# M101X.net
KiCad netlist of a schematic drawn in EAGLE
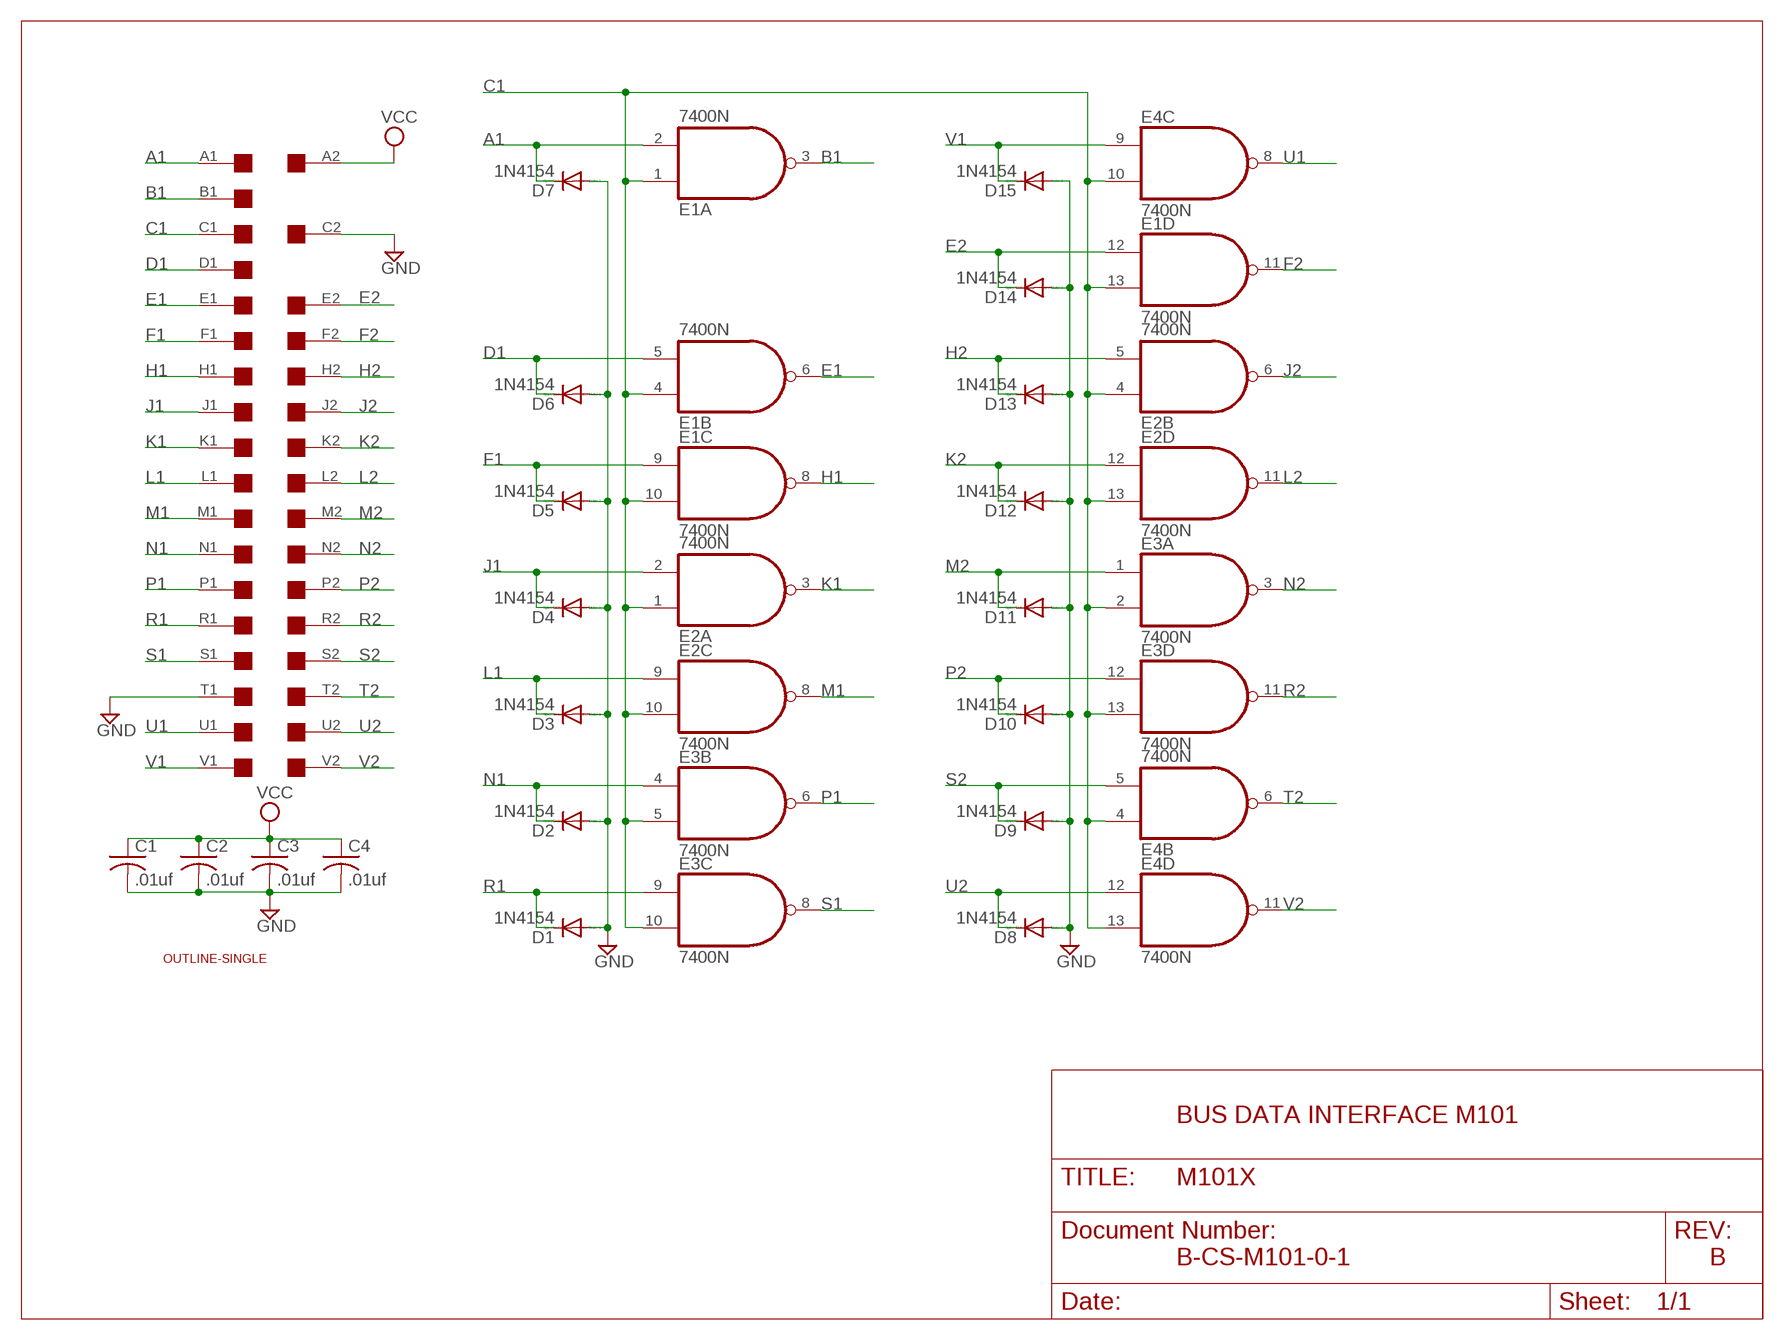
[diagram p0: schematic, sheet 1]

(export (version "E")
  (design (tool "Eeschema 10.0.6"))
  (components
    (comp (ref "C1")
      (value ".01uf")
      (footprint "eagle-import:C050-025X075")
      (libsource (lib "eagle-import") (part "C-US050-025X075"))
    )
    (comp (ref "C2")
      (value ".01uf")
      (footprint "eagle-import:C050-025X075")
      (libsource (lib "eagle-import") (part "C-US050-025X075"))
    )
    (comp (ref "C3")
      (value ".01uf")
      (footprint "eagle-import:C050-025X075")
      (libsource (lib "eagle-import") (part "C-US050-025X075"))
    )
    (comp (ref "C4")
      (value ".01uf")
      (footprint "eagle-import:C050-025X075")
      (libsource (lib "eagle-import") (part "C-US050-025X075"))
    )
    (comp (ref "D1")
      (value "1N4154")
      (footprint "eagle-import:DO35-10")
      (libsource (lib "eagle-import") (part "1N4148DO35-10"))
    )
    (comp (ref "D2")
      (value "1N4154")
      (footprint "eagle-import:DO35-10")
      (libsource (lib "eagle-import") (part "1N4148DO35-10"))
    )
    (comp (ref "D3")
      (value "1N4154")
      (footprint "eagle-import:DO35-10")
      (libsource (lib "eagle-import") (part "1N4148DO35-10"))
    )
    (comp (ref "D4")
      (value "1N4154")
      (footprint "eagle-import:DO35-10")
      (libsource (lib "eagle-import") (part "1N4148DO35-10"))
    )
    (comp (ref "D5")
      (value "1N4154")
      (footprint "eagle-import:DO35-10")
      (libsource (lib "eagle-import") (part "1N4148DO35-10"))
    )
    (comp (ref "D6")
      (value "1N4154")
      (footprint "eagle-import:DO35-10")
      (libsource (lib "eagle-import") (part "1N4148DO35-10"))
    )
    (comp (ref "D7")
      (value "1N4154")
      (footprint "eagle-import:DO35-10")
      (libsource (lib "eagle-import") (part "1N4148DO35-10"))
    )
    (comp (ref "D8")
      (value "1N4154")
      (footprint "eagle-import:DO35-10")
      (libsource (lib "eagle-import") (part "1N4148DO35-10"))
    )
    (comp (ref "D9")
      (value "1N4154")
      (footprint "eagle-import:DO35-10")
      (libsource (lib "eagle-import") (part "1N4148DO35-10"))
    )
    (comp (ref "D10")
      (value "1N4154")
      (footprint "eagle-import:DO35-10")
      (libsource (lib "eagle-import") (part "1N4148DO35-10"))
    )
    (comp (ref "D11")
      (value "1N4154")
      (footprint "eagle-import:DO35-10")
      (libsource (lib "eagle-import") (part "1N4148DO35-10"))
    )
    (comp (ref "D12")
      (value "1N4154")
      (footprint "eagle-import:DO35-10")
      (libsource (lib "eagle-import") (part "1N4148DO35-10"))
    )
    (comp (ref "D13")
      (value "1N4154")
      (footprint "eagle-import:DO35-10")
      (libsource (lib "eagle-import") (part "1N4148DO35-10"))
    )
    (comp (ref "D14")
      (value "1N4154")
      (footprint "eagle-import:DO35-10")
      (libsource (lib "eagle-import") (part "1N4148DO35-10"))
    )
    (comp (ref "D15")
      (value "1N4154")
      (footprint "eagle-import:DO35-10")
      (libsource (lib "eagle-import") (part "1N4148DO35-10"))
    )
    (comp (ref "E1")
      (value "7400N")
      (footprint "eagle-import:DIL14")
      (libsource (lib "eagle-import") (part "7400N"))
    )
    (comp (ref "E2")
      (value "7400N")
      (footprint "eagle-import:DIL14")
      (libsource (lib "eagle-import") (part "7400N"))
    )
    (comp (ref "E3")
      (value "7400N")
      (footprint "eagle-import:DIL14")
      (libsource (lib "eagle-import") (part "7400N"))
    )
    (comp (ref "E4")
      (value "7400N")
      (footprint "eagle-import:DIL14")
      (libsource (lib "eagle-import") (part "7400N"))
    )
    (comp (ref "U$1")
      (value "SINGLE")
      (footprint "eagle-import:EDGE-CON2")
      (libsource (lib "eagle-import") (part "SINGLE"))
    )
    (comp (ref "U$4")
      (value "OUTLINE-SINGLE")
      (footprint "eagle-import:SINGLE")
      (libsource (lib "eagle-import") (part "OUTLINE-SINGLE"))
    )
  )
  (nets
    (net (code "1") (name "/A1") (class "Default")
      (node (ref "D7") (pin "C") (pinfunction "C_C") (pintype "passive"))
      (node (ref "E1") (pin "2") (pinfunction "I1_2") (pintype "input"))
      (node (ref "U$1") (pin "A1") (pinfunction "1_A1") (pintype "bidirectional"))
    )
    (net (code "2") (name "/B1") (class "Default")
      (node (ref "E1") (pin "3") (pinfunction "O_3") (pintype "output"))
      (node (ref "U$1") (pin "B1") (pinfunction "1_B1") (pintype "bidirectional"))
    )
    (net (code "3") (name "/C1") (class "Default")
      (node (ref "E1") (pin "1") (pinfunction "I0_1") (pintype "input"))
      (node (ref "E1") (pin "10") (pinfunction "I1_10") (pintype "input"))
      (node (ref "E1") (pin "13") (pinfunction "I1_13") (pintype "input"))
      (node (ref "E1") (pin "4") (pinfunction "I0_4") (pintype "input"))
      (node (ref "E2") (pin "1") (pinfunction "I0_1") (pintype "input"))
      (node (ref "E2") (pin "10") (pinfunction "I1_10") (pintype "input"))
      (node (ref "E2") (pin "13") (pinfunction "I1_13") (pintype "input"))
      (node (ref "E2") (pin "4") (pinfunction "I0_4") (pintype "input"))
      (node (ref "E3") (pin "10") (pinfunction "I1_10") (pintype "input"))
      (node (ref "E3") (pin "13") (pinfunction "I1_13") (pintype "input"))
      (node (ref "E3") (pin "2") (pinfunction "I1_2") (pintype "input"))
      (node (ref "E3") (pin "5") (pinfunction "I1_5") (pintype "input"))
      (node (ref "E4") (pin "10") (pinfunction "I1_10") (pintype "input"))
      (node (ref "E4") (pin "13") (pinfunction "I1_13") (pintype "input"))
      (node (ref "E4") (pin "4") (pinfunction "I0_4") (pintype "input"))
      (node (ref "U$1") (pin "C1") (pinfunction "1_C1") (pintype "bidirectional"))
    )
    (net (code "4") (name "/D1") (class "Default")
      (node (ref "D6") (pin "C") (pinfunction "C_C") (pintype "passive"))
      (node (ref "E1") (pin "5") (pinfunction "I1_5") (pintype "input"))
      (node (ref "U$1") (pin "D1") (pinfunction "1_D1") (pintype "bidirectional"))
    )
    (net (code "5") (name "/E1") (class "Default")
      (node (ref "E1") (pin "6") (pinfunction "O_6") (pintype "output"))
      (node (ref "U$1") (pin "E1") (pinfunction "1_E1") (pintype "bidirectional"))
    )
    (net (code "6") (name "/E2") (class "Default")
      (node (ref "D14") (pin "C") (pinfunction "C_C") (pintype "passive"))
      (node (ref "E1") (pin "12") (pinfunction "I0_12") (pintype "input"))
      (node (ref "U$1") (pin "E2") (pinfunction "1_E2") (pintype "bidirectional"))
    )
    (net (code "7") (name "/F1") (class "Default")
      (node (ref "D5") (pin "C") (pinfunction "C_C") (pintype "passive"))
      (node (ref "E1") (pin "9") (pinfunction "I0_9") (pintype "input"))
      (node (ref "U$1") (pin "F1") (pinfunction "1_F1") (pintype "bidirectional"))
    )
    (net (code "8") (name "/F2") (class "Default")
      (node (ref "E1") (pin "11") (pinfunction "O_11") (pintype "output"))
      (node (ref "U$1") (pin "F2") (pinfunction "1_F2") (pintype "bidirectional"))
    )
    (net (code "9") (name "/H1") (class "Default")
      (node (ref "E1") (pin "8") (pinfunction "O_8") (pintype "output"))
      (node (ref "U$1") (pin "H1") (pinfunction "1_H1") (pintype "bidirectional"))
    )
    (net (code "10") (name "/H2") (class "Default")
      (node (ref "D13") (pin "C") (pinfunction "C_C") (pintype "passive"))
      (node (ref "E2") (pin "5") (pinfunction "I1_5") (pintype "input"))
      (node (ref "U$1") (pin "H2") (pinfunction "1_H2") (pintype "bidirectional"))
    )
    (net (code "11") (name "/J1") (class "Default")
      (node (ref "D4") (pin "C") (pinfunction "C_C") (pintype "passive"))
      (node (ref "E2") (pin "2") (pinfunction "I1_2") (pintype "input"))
      (node (ref "U$1") (pin "J1") (pinfunction "1_J1") (pintype "bidirectional"))
    )
    (net (code "12") (name "/J2") (class "Default")
      (node (ref "E2") (pin "6") (pinfunction "O_6") (pintype "output"))
      (node (ref "U$1") (pin "J2") (pinfunction "1_J2") (pintype "bidirectional"))
    )
    (net (code "13") (name "/K1") (class "Default")
      (node (ref "E2") (pin "3") (pinfunction "O_3") (pintype "output"))
      (node (ref "U$1") (pin "K1") (pinfunction "1_K1") (pintype "bidirectional"))
    )
    (net (code "14") (name "/K2") (class "Default")
      (node (ref "D12") (pin "C") (pinfunction "C_C") (pintype "passive"))
      (node (ref "E2") (pin "12") (pinfunction "I0_12") (pintype "input"))
      (node (ref "U$1") (pin "K2") (pinfunction "1_K2") (pintype "bidirectional"))
    )
    (net (code "15") (name "/L1") (class "Default")
      (node (ref "D3") (pin "C") (pinfunction "C_C") (pintype "passive"))
      (node (ref "E2") (pin "9") (pinfunction "I0_9") (pintype "input"))
      (node (ref "U$1") (pin "L1") (pinfunction "1_L1") (pintype "bidirectional"))
    )
    (net (code "16") (name "/L2") (class "Default")
      (node (ref "E2") (pin "11") (pinfunction "O_11") (pintype "output"))
      (node (ref "U$1") (pin "L2") (pinfunction "1_L2") (pintype "bidirectional"))
    )
    (net (code "17") (name "/M1") (class "Default")
      (node (ref "E2") (pin "8") (pinfunction "O_8") (pintype "output"))
      (node (ref "U$1") (pin "M1") (pinfunction "1_M1") (pintype "bidirectional"))
    )
    (net (code "18") (name "/M2") (class "Default")
      (node (ref "D11") (pin "C") (pinfunction "C_C") (pintype "passive"))
      (node (ref "E3") (pin "1") (pinfunction "I0_1") (pintype "input"))
      (node (ref "U$1") (pin "M2") (pinfunction "1_M2") (pintype "bidirectional"))
    )
    (net (code "19") (name "/N1") (class "Default")
      (node (ref "D2") (pin "C") (pinfunction "C_C") (pintype "passive"))
      (node (ref "E3") (pin "4") (pinfunction "I0_4") (pintype "input"))
      (node (ref "U$1") (pin "N1") (pinfunction "1_N1") (pintype "bidirectional"))
    )
    (net (code "20") (name "/N2") (class "Default")
      (node (ref "E3") (pin "3") (pinfunction "O_3") (pintype "output"))
      (node (ref "U$1") (pin "N2") (pinfunction "1_N2") (pintype "bidirectional"))
    )
    (net (code "21") (name "/P1") (class "Default")
      (node (ref "E3") (pin "6") (pinfunction "O_6") (pintype "output"))
      (node (ref "U$1") (pin "P1") (pinfunction "1_P1") (pintype "bidirectional"))
    )
    (net (code "22") (name "/P2") (class "Default")
      (node (ref "D10") (pin "C") (pinfunction "C_C") (pintype "passive"))
      (node (ref "E3") (pin "12") (pinfunction "I0_12") (pintype "input"))
      (node (ref "U$1") (pin "P2") (pinfunction "1_P2") (pintype "bidirectional"))
    )
    (net (code "23") (name "/R1") (class "Default")
      (node (ref "D1") (pin "C") (pinfunction "C_C") (pintype "passive"))
      (node (ref "E3") (pin "9") (pinfunction "I0_9") (pintype "input"))
      (node (ref "U$1") (pin "R1") (pinfunction "1_R1") (pintype "bidirectional"))
    )
    (net (code "24") (name "/R2") (class "Default")
      (node (ref "E3") (pin "11") (pinfunction "O_11") (pintype "output"))
      (node (ref "U$1") (pin "R2") (pinfunction "1_R2") (pintype "bidirectional"))
    )
    (net (code "25") (name "/S1") (class "Default")
      (node (ref "E3") (pin "8") (pinfunction "O_8") (pintype "output"))
      (node (ref "U$1") (pin "S1") (pinfunction "1_S1") (pintype "bidirectional"))
    )
    (net (code "26") (name "/S2") (class "Default")
      (node (ref "D9") (pin "C") (pinfunction "C_C") (pintype "passive"))
      (node (ref "E4") (pin "5") (pinfunction "I1_5") (pintype "input"))
      (node (ref "U$1") (pin "S2") (pinfunction "1_S2") (pintype "bidirectional"))
    )
    (net (code "27") (name "/T2") (class "Default")
      (node (ref "E4") (pin "6") (pinfunction "O_6") (pintype "output"))
      (node (ref "U$1") (pin "T2") (pinfunction "1_T2") (pintype "bidirectional"))
    )
    (net (code "28") (name "/U1") (class "Default")
      (node (ref "E4") (pin "8") (pinfunction "O_8") (pintype "output"))
      (node (ref "U$1") (pin "U1") (pinfunction "1_U1") (pintype "bidirectional"))
    )
    (net (code "29") (name "/U2") (class "Default")
      (node (ref "D8") (pin "C") (pinfunction "C_C") (pintype "passive"))
      (node (ref "E4") (pin "12") (pinfunction "I0_12") (pintype "input"))
      (node (ref "U$1") (pin "U2") (pinfunction "1_U2") (pintype "bidirectional"))
    )
    (net (code "30") (name "/V1") (class "Default")
      (node (ref "D15") (pin "C") (pinfunction "C_C") (pintype "passive"))
      (node (ref "E4") (pin "9") (pinfunction "I0_9") (pintype "input"))
      (node (ref "U$1") (pin "V1") (pinfunction "1_V1") (pintype "bidirectional"))
    )
    (net (code "31") (name "/V2") (class "Default")
      (node (ref "E4") (pin "11") (pinfunction "O_11") (pintype "output"))
      (node (ref "U$1") (pin "V2") (pinfunction "1_V2") (pintype "bidirectional"))
    )
    (net (code "32") (name "GND") (class "Default")
      (node (ref "C1") (pin "2") (pinfunction "2_2") (pintype "passive"))
      (node (ref "C2") (pin "2") (pinfunction "2_2") (pintype "passive"))
      (node (ref "C3") (pin "2") (pinfunction "2_2") (pintype "passive"))
      (node (ref "C4") (pin "2") (pinfunction "2_2") (pintype "passive"))
      (node (ref "D1") (pin "A") (pinfunction "A_A") (pintype "passive"))
      (node (ref "D10") (pin "A") (pinfunction "A_A") (pintype "passive"))
      (node (ref "D11") (pin "A") (pinfunction "A_A") (pintype "passive"))
      (node (ref "D12") (pin "A") (pinfunction "A_A") (pintype "passive"))
      (node (ref "D13") (pin "A") (pinfunction "A_A") (pintype "passive"))
      (node (ref "D14") (pin "A") (pinfunction "A_A") (pintype "passive"))
      (node (ref "D15") (pin "A") (pinfunction "A_A") (pintype "passive"))
      (node (ref "D2") (pin "A") (pinfunction "A_A") (pintype "passive"))
      (node (ref "D3") (pin "A") (pinfunction "A_A") (pintype "passive"))
      (node (ref "D4") (pin "A") (pinfunction "A_A") (pintype "passive"))
      (node (ref "D5") (pin "A") (pinfunction "A_A") (pintype "passive"))
      (node (ref "D6") (pin "A") (pinfunction "A_A") (pintype "passive"))
      (node (ref "D7") (pin "A") (pinfunction "A_A") (pintype "passive"))
      (node (ref "D8") (pin "A") (pinfunction "A_A") (pintype "passive"))
      (node (ref "D9") (pin "A") (pinfunction "A_A") (pintype "passive"))
      (node (ref "U$1") (pin "C2") (pinfunction "1_C2") (pintype "bidirectional"))
      (node (ref "U$1") (pin "T1") (pinfunction "1_T1") (pintype "bidirectional"))
    )
    (net (code "33") (name "VCC") (class "Default")
      (node (ref "C1") (pin "1") (pinfunction "1_1") (pintype "passive"))
      (node (ref "C2") (pin "1") (pinfunction "1_1") (pintype "passive"))
      (node (ref "C3") (pin "1") (pinfunction "1_1") (pintype "passive"))
      (node (ref "C4") (pin "1") (pinfunction "1_1") (pintype "passive"))
      (node (ref "U$1") (pin "A2") (pinfunction "1_A2") (pintype "bidirectional"))
    )
  )
)
